# 1-Schematic_get_me_some_thin_mint_season.net
KiCad netlist of a schematic drawn in EasyEDA
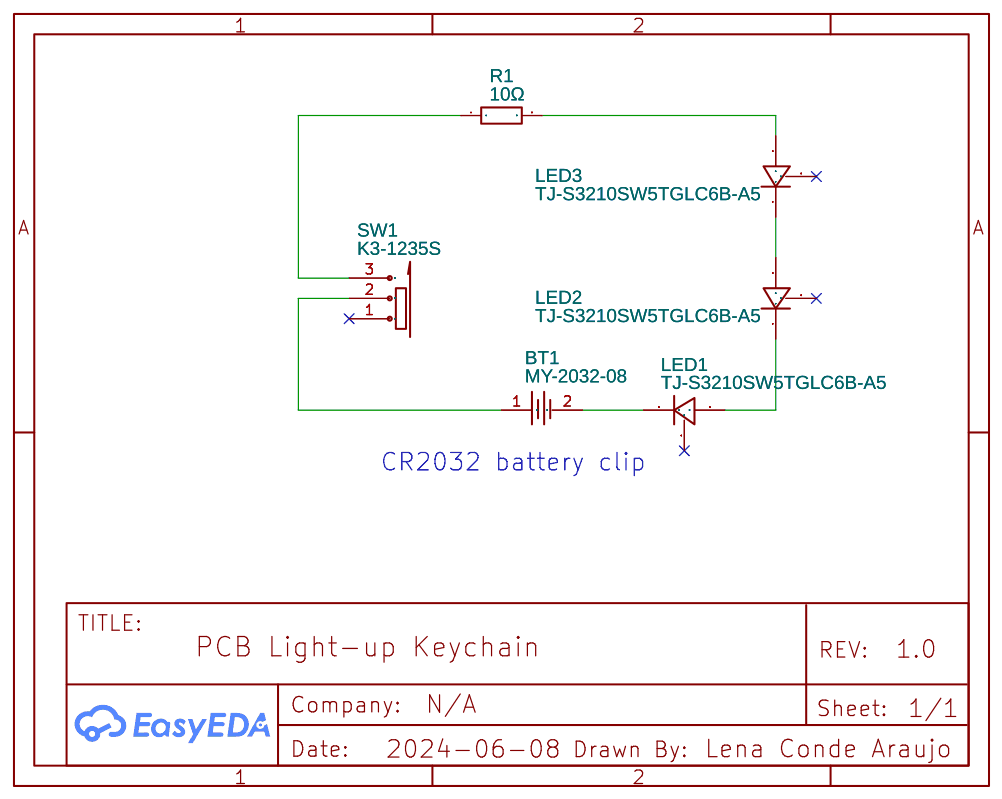
[diagram p0: schematic sheet]

(export (version "E")
  (design (tool "Eeschema 10.0.6"))
  (components
    (comp (ref "BT1")
      (value "MY-2032-08")
      (fields (field (name "Manufacturer") "MYOUNG(美阳)"))
      (libsource (lib "") (part "MY-2032-08"))
    )
    (comp (ref "LED1")
      (value "TJ-S3210SW5TGLC6B-A5")
      (fields (field (name "Manufacturer") "TOGIALED(统佳)"))
      (libsource (lib "") (part "TJ-S3210SW5TGLC6B-A5_1"))
    )
    (comp (ref "LED2")
      (value "TJ-S3210SW5TGLC6B-A5")
      (fields (field (name "Manufacturer") "TOGIALED(统佳)"))
      (libsource (lib "") (part "TJ-S3210SW5TGLC6B-A5"))
    )
    (comp (ref "LED3")
      (value "TJ-S3210SW5TGLC6B-A5")
      (fields (field (name "Manufacturer") "TOGIALED(统佳)"))
      (libsource (lib "") (part "TJ-S3210SW5TGLC6B-A5"))
    )
    (comp (ref "R1")
      (value "10Ω")
      (fields
        (field (name "Manufacturer Part") "0603WAF100JT5E")
        (field (name "Manufacturer") "UNI-ROYAL(厚声)")
      )
      (libsource (lib "") (part "0603WAF100JT5E"))
    )
    (comp (ref "SW1")
      (value "K3-1235S")
      (fields (field (name "Manufacturer Part") "K3-1235S-F1") (field (name "Manufacturer") "韩国韩荣"))
      (libsource (lib "") (part "K3-1235S"))
    )
  )
  (nets
    (net (code "1") (name "Net-(BT1-Pad1)") (class "Default")
      (node (ref "BT1") (pin "1") (pinfunction "1_1") (pintype "input"))
      (node (ref "SW1") (pin "2") (pinfunction "2_2") (pintype "unspecified"))
    )
    (net (code "2") (name "Net-(BT1-Pad2)") (class "Default")
      (node (ref "BT1") (pin "2") (pinfunction "2_2") (pintype "input"))
      (node (ref "LED1") (pin "1") (pinfunction "1_1") (pintype "unspecified"))
    )
    (net (code "3") (name "Net-(LED1-Pad2)") (class "Default")
      (node (ref "LED1") (pin "2") (pinfunction "2_2") (pintype "unspecified"))
      (node (ref "LED2") (pin "1") (pinfunction "1_1") (pintype "unspecified"))
    )
    (net (code "4") (name "Net-(LED2-Pad2)") (class "Default")
      (node (ref "LED2") (pin "2") (pinfunction "2_2") (pintype "unspecified"))
      (node (ref "LED3") (pin "1") (pinfunction "1_1") (pintype "unspecified"))
    )
    (net (code "5") (name "Net-(LED3-Pad2)") (class "Default")
      (node (ref "LED3") (pin "2") (pinfunction "2_2") (pintype "unspecified"))
      (node (ref "R1") (pin "2") (pinfunction "2_2") (pintype "input"))
    )
    (net (code "6") (name "Net-(R1-Pad1)") (class "Default")
      (node (ref "R1") (pin "1") (pinfunction "1_1") (pintype "input"))
      (node (ref "SW1") (pin "3") (pinfunction "3_3") (pintype "unspecified"))
    )
    (net (code "7") (name "unconnected-(LED1-Pad3)") (class "Default")
      (node (ref "LED1") (pin "3") (pinfunction "3_3") (pintype "unspecified+no_connect"))
    )
    (net (code "8") (name "unconnected-(LED2-Pad3)") (class "Default")
      (node (ref "LED2") (pin "3") (pinfunction "3_3") (pintype "unspecified+no_connect"))
    )
    (net (code "9") (name "unconnected-(LED3-Pad3)") (class "Default")
      (node (ref "LED3") (pin "3") (pinfunction "3_3") (pintype "unspecified+no_connect"))
    )
    (net (code "10") (name "unconnected-(SW1-Pad1)") (class "Default")
      (node (ref "SW1") (pin "1") (pinfunction "1_1") (pintype "unspecified+no_connect"))
    )
  )
)
